# ESP32_breakout_v1.net
KiCad netlist of a schematic drawn in EAGLE
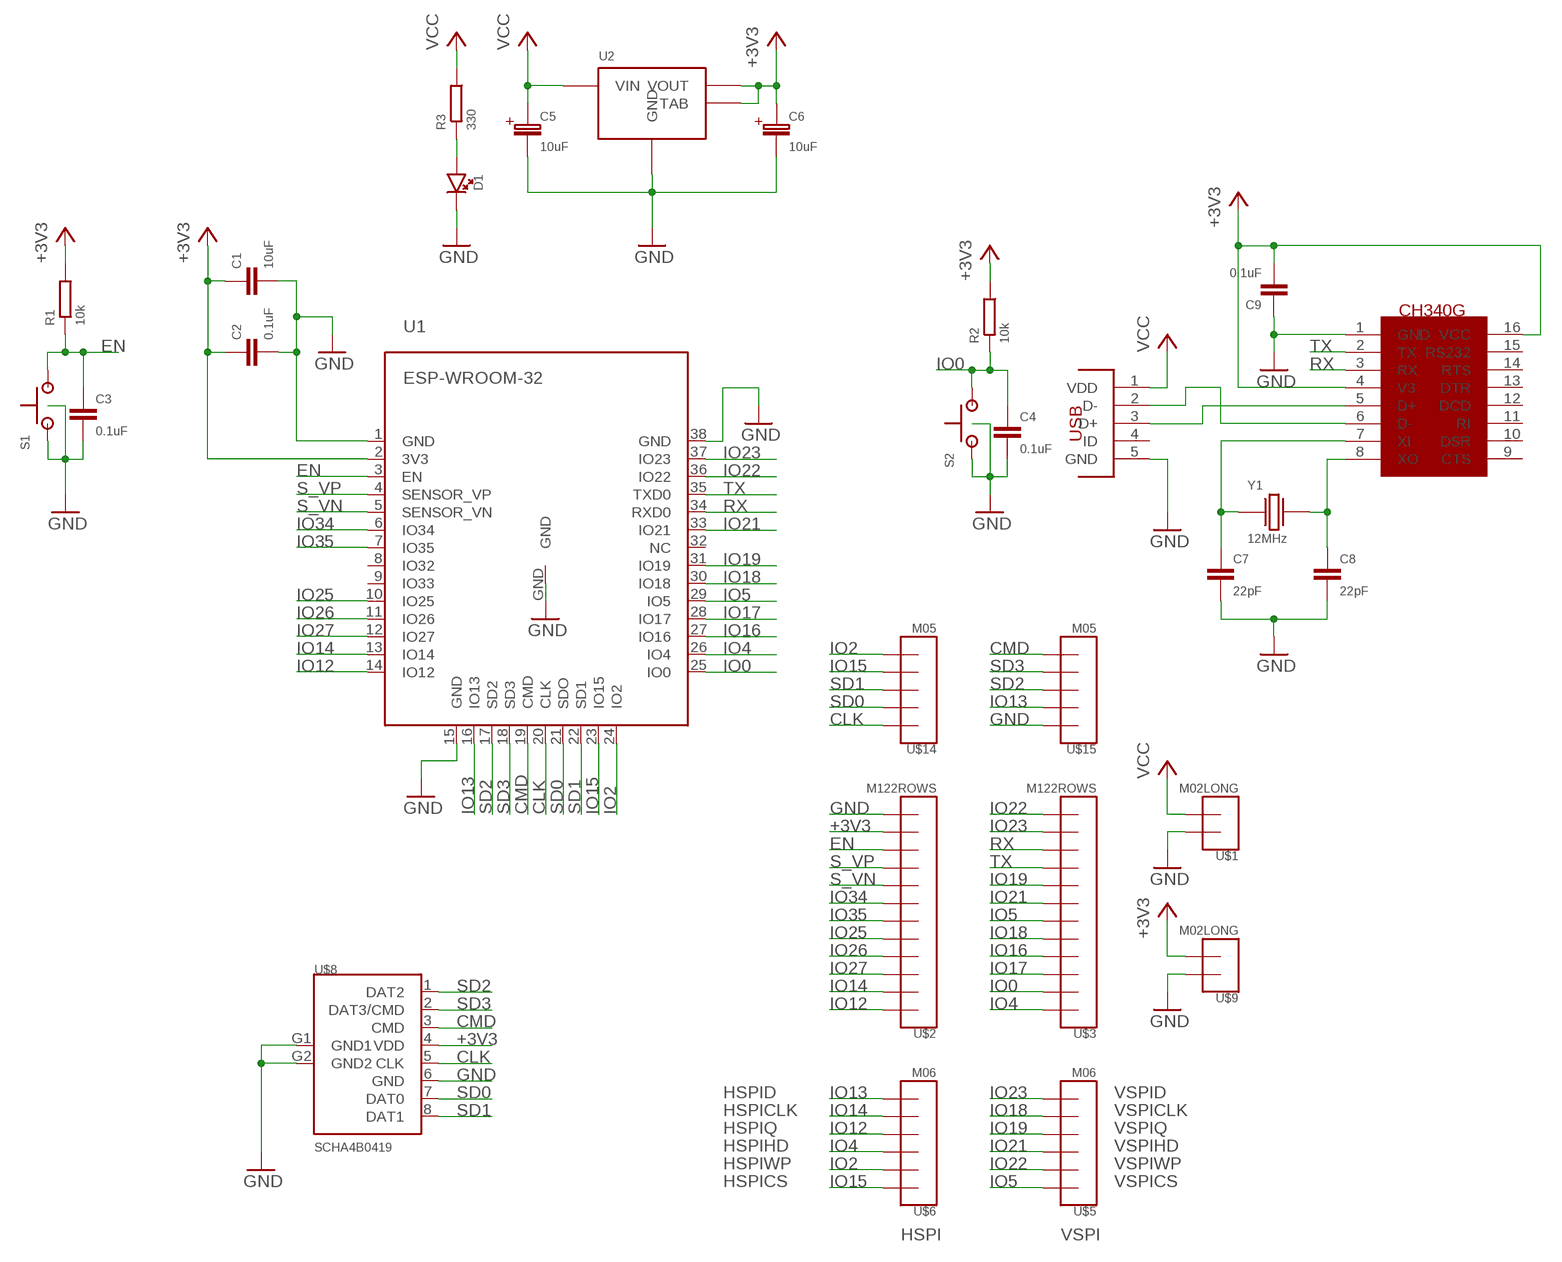
[diagram p0: schematic, sheet 1]

(export (version "E")
  (design (tool "Eeschema 10.0.6"))
  (components
    (comp (ref "C1")
      (value "10uF")
      (footprint "eagle-import:CAP-0603")
      (libsource (lib "eagle-import") (part "CAP0603"))
    )
    (comp (ref "C2")
      (value "0.1uF")
      (footprint "eagle-import:CAP-0603")
      (libsource (lib "eagle-import") (part "CAP0603"))
    )
    (comp (ref "C3")
      (value "0.1uF")
      (footprint "eagle-import:CAP-0603")
      (libsource (lib "eagle-import") (part "CAP0603"))
    )
    (comp (ref "C4")
      (value "0.1uF")
      (footprint "eagle-import:CAP-0603")
      (libsource (lib "eagle-import") (part "CAP0603"))
    )
    (comp (ref "C5")
      (value "10uF")
      (footprint "eagle-import:B-3528")
      (libsource (lib "eagle-import") (part "CAP-POLARCASEB-3528"))
    )
    (comp (ref "C6")
      (value "10uF")
      (footprint "eagle-import:B-3528")
      (libsource (lib "eagle-import") (part "CAP-POLARCASEB-3528"))
    )
    (comp (ref "C7")
      (value "22pF")
      (footprint "eagle-import:CAP-0603")
      (libsource (lib "eagle-import") (part "CAP0603"))
    )
    (comp (ref "C8")
      (value "22pF")
      (footprint "eagle-import:CAP-0603")
      (libsource (lib "eagle-import") (part "CAP0603"))
    )
    (comp (ref "C9")
      (value "0.1uF")
      (footprint "eagle-import:CAP-0603")
      (libsource (lib "eagle-import") (part "CAP0603"))
    )
    (comp (ref "D1")
      (value "LED1206")
      (footprint "eagle-import:LED-1206")
      (libsource (lib "eagle-import") (part "LED1206"))
    )
    (comp (ref "R1")
      (value "10k")
      (footprint "eagle-import:RES-0603")
      (libsource (lib "eagle-import") (part "RESISTOR0603"))
    )
    (comp (ref "R2")
      (value "10k")
      (footprint "eagle-import:RES-0603")
      (libsource (lib "eagle-import") (part "RESISTOR0603"))
    )
    (comp (ref "R3")
      (value "330")
      (footprint "eagle-import:RES-0603")
      (libsource (lib "eagle-import") (part "RESISTOR0603"))
    )
    (comp (ref "S1")
      (value "SKHMQME010")
      (footprint "eagle-import:SKHMQME010")
      (libsource (lib "eagle-import") (part "SKHMQME010"))
    )
    (comp (ref "S2")
      (value "SKHMQME010")
      (footprint "eagle-import:SKHMQME010")
      (libsource (lib "eagle-import") (part "SKHMQME010"))
    )
    (comp (ref "U$1")
      (value "M02LONG")
      (footprint "eagle-import:1X02-LONG")
      (libsource (lib "eagle-import") (part "M02LONG"))
    )
    (comp (ref "U$2")
      (value "M122ROWS")
      (footprint "eagle-import:2X06")
      (libsource (lib "eagle-import") (part "M122ROWS"))
    )
    (comp (ref "U$3")
      (value "M122ROWS")
      (footprint "eagle-import:2X06")
      (libsource (lib "eagle-import") (part "M122ROWS"))
    )
    (comp (ref "U$4")
      (value "MOLEX_USBMICRO")
      (footprint "eagle-import:MOLEX_47346-001")
      (libsource (lib "eagle-import") (part "MOLEX_USBMICRO"))
    )
    (comp (ref "U$5")
      (value "M06")
      (footprint "eagle-import:1X06")
      (libsource (lib "eagle-import") (part "M06"))
    )
    (comp (ref "U$6")
      (value "M06")
      (footprint "eagle-import:1X06")
      (libsource (lib "eagle-import") (part "M06"))
    )
    (comp (ref "U$7")
      (value "CH340G")
      (footprint "eagle-import:SOIC16")
      (libsource (lib "eagle-import") (part "CH340G"))
    )
    (comp (ref "U$8")
      (value "SCHA4B0419")
      (footprint "eagle-import:MICROSD_SCHA4B0419")
      (libsource (lib "eagle-import") (part "SCHA4B0419"))
    )
    (comp (ref "U$9")
      (value "M02LONG")
      (footprint "eagle-import:1X02-LONG")
      (libsource (lib "eagle-import") (part "M02LONG"))
    )
    (comp (ref "U$14")
      (value "M05")
      (footprint "eagle-import:1X05")
      (libsource (lib "eagle-import") (part "M05"))
    )
    (comp (ref "U$15")
      (value "M05")
      (footprint "eagle-import:1X05")
      (libsource (lib "eagle-import") (part "M05"))
    )
    (comp (ref "U1")
      (value "ESP-WROOM-32")
      (footprint "eagle-import:ESP-WROOM-32")
      (libsource (lib "eagle-import") (part "ESP-WROOM-32"))
    )
    (comp (ref "U2")
      (value "NCP-1117")
      (footprint "eagle-import:SOT-223-4")
      (libsource (lib "eagle-import") (part "NCP-1117"))
    )
    (comp (ref "Y1")
      (value "12MHz")
      (footprint "eagle-import:HC-49_US")
      (libsource (lib "eagle-import") (part "ABLS-12MHZ-B2-T"))
    )
  )
  (nets
    (net (code "1") (name "+3V3") (class "Default")
      (node (ref "C1") (pin "1") (pinfunction "1_1") (pintype "passive"))
      (node (ref "C2") (pin "1") (pinfunction "1_1") (pintype "passive"))
      (node (ref "C6") (pin "P") (pinfunction "P_P") (pintype "passive"))
      (node (ref "C9") (pin "2") (pinfunction "2_2") (pintype "passive"))
      (node (ref "R1") (pin "2") (pinfunction "2_2") (pintype "passive"))
      (node (ref "R2") (pin "2") (pinfunction "2_2") (pintype "passive"))
      (node (ref "U$2") (pin "11") (pinfunction "11_11") (pintype "bidirectional"))
      (node (ref "U$7") (pin "16") (pinfunction "VCC_16") (pintype "bidirectional"))
      (node (ref "U$7") (pin "4") (pinfunction "V3_4") (pintype "bidirectional"))
      (node (ref "U$8") (pin "4") (pinfunction "VDD_4") (pintype "bidirectional"))
      (node (ref "U$9") (pin "2") (pinfunction "2_2") (pintype "bidirectional"))
      (node (ref "U1") (pin "2") (pinfunction "3V3_2") (pintype "bidirectional"))
      (node (ref "U2") (pin "2") (pinfunction "VOUT_2") (pintype "power_in"))
      (node (ref "U2") (pin "PAD") (pinfunction "TAB_PAD") (pintype "power_in"))
    )
    (net (code "2") (name "/CLK") (class "Default")
      (node (ref "U$14") (pin "1") (pinfunction "1_1") (pintype "bidirectional"))
      (node (ref "U$8") (pin "5") (pinfunction "CLK_5") (pintype "bidirectional"))
      (node (ref "U1") (pin "20") (pinfunction "CLK_20") (pintype "bidirectional"))
    )
    (net (code "3") (name "/CMD") (class "Default")
      (node (ref "U$15") (pin "5") (pinfunction "5_5") (pintype "bidirectional"))
      (node (ref "U$8") (pin "3") (pinfunction "CMD_3") (pintype "bidirectional"))
      (node (ref "U1") (pin "19") (pinfunction "CMD_19") (pintype "bidirectional"))
    )
    (net (code "4") (name "/EN") (class "Default")
      (node (ref "C3") (pin "1") (pinfunction "1_1") (pintype "passive"))
      (node (ref "R1") (pin "1") (pinfunction "1_1") (pintype "passive"))
      (node (ref "S1") (pin "3") (pinfunction "2_3") (pintype "bidirectional"))
      (node (ref "U$2") (pin "10") (pinfunction "10_10") (pintype "bidirectional"))
      (node (ref "U1") (pin "3") (pinfunction "EN_3") (pintype "bidirectional"))
    )
    (net (code "5") (name "/IO0") (class "Default")
      (node (ref "C4") (pin "1") (pinfunction "1_1") (pintype "passive"))
      (node (ref "R2") (pin "1") (pinfunction "1_1") (pintype "passive"))
      (node (ref "S2") (pin "3") (pinfunction "2_3") (pintype "bidirectional"))
      (node (ref "U$3") (pin "2") (pinfunction "2_2") (pintype "bidirectional"))
      (node (ref "U1") (pin "25") (pinfunction "IO0_25") (pintype "bidirectional"))
    )
    (net (code "6") (name "/IO2") (class "Default")
      (node (ref "U$14") (pin "5") (pinfunction "5_5") (pintype "bidirectional"))
      (node (ref "U$6") (pin "2") (pinfunction "2_2") (pintype "bidirectional"))
      (node (ref "U1") (pin "24") (pinfunction "IO2_24") (pintype "bidirectional"))
    )
    (net (code "7") (name "/IO4") (class "Default")
      (node (ref "U$3") (pin "1") (pinfunction "1_1") (pintype "bidirectional"))
      (node (ref "U$6") (pin "3") (pinfunction "3_3") (pintype "bidirectional"))
      (node (ref "U1") (pin "26") (pinfunction "IO4_26") (pintype "bidirectional"))
    )
    (net (code "8") (name "/IO5") (class "Default")
      (node (ref "U$3") (pin "6") (pinfunction "6_6") (pintype "bidirectional"))
      (node (ref "U$5") (pin "1") (pinfunction "1_1") (pintype "bidirectional"))
      (node (ref "U1") (pin "29") (pinfunction "IO5_29") (pintype "bidirectional"))
    )
    (net (code "9") (name "/IO12") (class "Default")
      (node (ref "U$2") (pin "1") (pinfunction "1_1") (pintype "bidirectional"))
      (node (ref "U$6") (pin "4") (pinfunction "4_4") (pintype "bidirectional"))
      (node (ref "U1") (pin "14") (pinfunction "IO12_14") (pintype "bidirectional"))
    )
    (net (code "10") (name "/IO13") (class "Default")
      (node (ref "U$15") (pin "2") (pinfunction "2_2") (pintype "bidirectional"))
      (node (ref "U$6") (pin "6") (pinfunction "6_6") (pintype "bidirectional"))
      (node (ref "U1") (pin "16") (pinfunction "IO13_16") (pintype "bidirectional"))
    )
    (net (code "11") (name "/IO14") (class "Default")
      (node (ref "U$2") (pin "2") (pinfunction "2_2") (pintype "bidirectional"))
      (node (ref "U$6") (pin "5") (pinfunction "5_5") (pintype "bidirectional"))
      (node (ref "U1") (pin "13") (pinfunction "IO14_13") (pintype "bidirectional"))
    )
    (net (code "12") (name "/IO15") (class "Default")
      (node (ref "U$14") (pin "4") (pinfunction "4_4") (pintype "bidirectional"))
      (node (ref "U$6") (pin "1") (pinfunction "1_1") (pintype "bidirectional"))
      (node (ref "U1") (pin "23") (pinfunction "IO15_23") (pintype "bidirectional"))
    )
    (net (code "13") (name "/IO16") (class "Default")
      (node (ref "U$3") (pin "4") (pinfunction "4_4") (pintype "bidirectional"))
      (node (ref "U1") (pin "27") (pinfunction "IO16_27") (pintype "bidirectional"))
    )
    (net (code "14") (name "/IO17") (class "Default")
      (node (ref "U$3") (pin "3") (pinfunction "3_3") (pintype "bidirectional"))
      (node (ref "U1") (pin "28") (pinfunction "IO17_28") (pintype "bidirectional"))
    )
    (net (code "15") (name "/IO18") (class "Default")
      (node (ref "U$3") (pin "5") (pinfunction "5_5") (pintype "bidirectional"))
      (node (ref "U$5") (pin "5") (pinfunction "5_5") (pintype "bidirectional"))
      (node (ref "U1") (pin "30") (pinfunction "IO18_30") (pintype "bidirectional"))
    )
    (net (code "16") (name "/IO19") (class "Default")
      (node (ref "U$3") (pin "8") (pinfunction "8_8") (pintype "bidirectional"))
      (node (ref "U$5") (pin "4") (pinfunction "4_4") (pintype "bidirectional"))
      (node (ref "U1") (pin "31") (pinfunction "IO19_31") (pintype "bidirectional"))
    )
    (net (code "17") (name "/IO21") (class "Default")
      (node (ref "U$3") (pin "7") (pinfunction "7_7") (pintype "bidirectional"))
      (node (ref "U$5") (pin "3") (pinfunction "3_3") (pintype "bidirectional"))
      (node (ref "U1") (pin "33") (pinfunction "IO21_33") (pintype "bidirectional"))
    )
    (net (code "18") (name "/IO22") (class "Default")
      (node (ref "U$3") (pin "12") (pinfunction "12_12") (pintype "bidirectional"))
      (node (ref "U$5") (pin "2") (pinfunction "2_2") (pintype "bidirectional"))
      (node (ref "U1") (pin "36") (pinfunction "IO22_36") (pintype "bidirectional"))
    )
    (net (code "19") (name "/IO23") (class "Default")
      (node (ref "U$3") (pin "11") (pinfunction "11_11") (pintype "bidirectional"))
      (node (ref "U$5") (pin "6") (pinfunction "6_6") (pintype "bidirectional"))
      (node (ref "U1") (pin "37") (pinfunction "IO23_37") (pintype "bidirectional"))
    )
    (net (code "20") (name "/IO25") (class "Default")
      (node (ref "U$2") (pin "5") (pinfunction "5_5") (pintype "bidirectional"))
      (node (ref "U1") (pin "10") (pinfunction "IO25_10") (pintype "bidirectional"))
    )
    (net (code "21") (name "/IO26") (class "Default")
      (node (ref "U$2") (pin "4") (pinfunction "4_4") (pintype "bidirectional"))
      (node (ref "U1") (pin "11") (pinfunction "IO26_11") (pintype "bidirectional"))
    )
    (net (code "22") (name "/IO27") (class "Default")
      (node (ref "U$2") (pin "3") (pinfunction "3_3") (pintype "bidirectional"))
      (node (ref "U1") (pin "12") (pinfunction "IO27_12") (pintype "bidirectional"))
    )
    (net (code "23") (name "/IO34") (class "Default")
      (node (ref "U$2") (pin "7") (pinfunction "7_7") (pintype "bidirectional"))
      (node (ref "U1") (pin "6") (pinfunction "IO34_6") (pintype "bidirectional"))
    )
    (net (code "24") (name "/IO35") (class "Default")
      (node (ref "U$2") (pin "6") (pinfunction "6_6") (pintype "bidirectional"))
      (node (ref "U1") (pin "7") (pinfunction "IO35_7") (pintype "bidirectional"))
    )
    (net (code "25") (name "/RX") (class "Default")
      (node (ref "U$3") (pin "10") (pinfunction "10_10") (pintype "bidirectional"))
      (node (ref "U$7") (pin "3") (pinfunction "RX_3") (pintype "bidirectional"))
      (node (ref "U1") (pin "34") (pinfunction "RXD0_34") (pintype "bidirectional"))
    )
    (net (code "26") (name "/SD0") (class "Default")
      (node (ref "U$14") (pin "2") (pinfunction "2_2") (pintype "bidirectional"))
      (node (ref "U$8") (pin "7") (pinfunction "DAT0_7") (pintype "bidirectional"))
      (node (ref "U1") (pin "21") (pinfunction "SDO_21") (pintype "bidirectional"))
    )
    (net (code "27") (name "/SD1") (class "Default")
      (node (ref "U$14") (pin "3") (pinfunction "3_3") (pintype "bidirectional"))
      (node (ref "U$8") (pin "8") (pinfunction "DAT1_8") (pintype "bidirectional"))
      (node (ref "U1") (pin "22") (pinfunction "SD1_22") (pintype "bidirectional"))
    )
    (net (code "28") (name "/SD2") (class "Default")
      (node (ref "U$15") (pin "3") (pinfunction "3_3") (pintype "bidirectional"))
      (node (ref "U$8") (pin "1") (pinfunction "DAT2_1") (pintype "bidirectional"))
      (node (ref "U1") (pin "17") (pinfunction "SD2_17") (pintype "bidirectional"))
    )
    (net (code "29") (name "/SD3") (class "Default")
      (node (ref "U$15") (pin "4") (pinfunction "4_4") (pintype "bidirectional"))
      (node (ref "U$8") (pin "2") (pinfunction "DAT3/CMD_2") (pintype "bidirectional"))
      (node (ref "U1") (pin "18") (pinfunction "SD3_18") (pintype "bidirectional"))
    )
    (net (code "30") (name "/S_VN") (class "Default")
      (node (ref "U$2") (pin "8") (pinfunction "8_8") (pintype "bidirectional"))
      (node (ref "U1") (pin "5") (pinfunction "SENSOR_VN_5") (pintype "bidirectional"))
    )
    (net (code "31") (name "/S_VP") (class "Default")
      (node (ref "U$2") (pin "9") (pinfunction "9_9") (pintype "bidirectional"))
      (node (ref "U1") (pin "4") (pinfunction "SENSOR_VP_4") (pintype "bidirectional"))
    )
    (net (code "32") (name "/TX") (class "Default")
      (node (ref "U$3") (pin "9") (pinfunction "9_9") (pintype "bidirectional"))
      (node (ref "U$7") (pin "2") (pinfunction "TX_2") (pintype "bidirectional"))
      (node (ref "U1") (pin "35") (pinfunction "TXD0_35") (pintype "bidirectional"))
    )
    (net (code "33") (name "GND") (class "Default")
      (node (ref "C1") (pin "2") (pinfunction "2_2") (pintype "passive"))
      (node (ref "C2") (pin "2") (pinfunction "2_2") (pintype "passive"))
      (node (ref "C3") (pin "2") (pinfunction "2_2") (pintype "passive"))
      (node (ref "C4") (pin "2") (pinfunction "2_2") (pintype "passive"))
      (node (ref "C5") (pin "N") (pinfunction "N_N") (pintype "passive"))
      (node (ref "C6") (pin "N") (pinfunction "N_N") (pintype "passive"))
      (node (ref "C7") (pin "2") (pinfunction "2_2") (pintype "passive"))
      (node (ref "C8") (pin "2") (pinfunction "2_2") (pintype "passive"))
      (node (ref "C9") (pin "1") (pinfunction "1_1") (pintype "passive"))
      (node (ref "D1") (pin "C") (pinfunction "C_C") (pintype "bidirectional"))
      (node (ref "S1") (pin "1") (pinfunction "1_1") (pintype "bidirectional"))
      (node (ref "S1") (pin "5") (pinfunction "3_5") (pintype "bidirectional"))
      (node (ref "S2") (pin "1") (pinfunction "1_1") (pintype "bidirectional"))
      (node (ref "S2") (pin "5") (pinfunction "3_5") (pintype "bidirectional"))
      (node (ref "U$1") (pin "1") (pinfunction "1_1") (pintype "bidirectional"))
      (node (ref "U$15") (pin "1") (pinfunction "1_1") (pintype "bidirectional"))
      (node (ref "U$2") (pin "12") (pinfunction "12_12") (pintype "bidirectional"))
      (node (ref "U$4") (pin "5") (pinfunction "GND_5") (pintype "bidirectional"))
      (node (ref "U$7") (pin "1") (pinfunction "GND_1") (pintype "bidirectional"))
      (node (ref "U$8") (pin "6") (pinfunction "GND_6") (pintype "bidirectional"))
      (node (ref "U$8") (pin "G1") (pinfunction "GND1_G1") (pintype "bidirectional"))
      (node (ref "U$8") (pin "G2") (pinfunction "GND2_G2") (pintype "bidirectional"))
      (node (ref "U$9") (pin "1") (pinfunction "1_1") (pintype "bidirectional"))
      (node (ref "U1") (pin "1") (pinfunction "GND_1") (pintype "bidirectional"))
      (node (ref "U1") (pin "15") (pinfunction "GND_15") (pintype "bidirectional"))
      (node (ref "U1") (pin "38") (pinfunction "GND_38") (pintype "bidirectional"))
      (node (ref "U1") (pin "GND") (pinfunction "GND_GND") (pintype "bidirectional"))
      (node (ref "U2") (pin "1") (pinfunction "GND_1") (pintype "power_in"))
    )
    (net (code "34") (name "Net-(D1-PadA)") (class "Default")
      (node (ref "D1") (pin "A") (pinfunction "A_A") (pintype "bidirectional"))
      (node (ref "R3") (pin "1") (pinfunction "1_1") (pintype "passive"))
    )
    (net (code "35") (name "Net-(U$4-D+)") (class "Default")
      (node (ref "U$4") (pin "3") (pinfunction "D+_3") (pintype "bidirectional"))
      (node (ref "U$7") (pin "5") (pinfunction "D+_5") (pintype "bidirectional"))
    )
    (net (code "36") (name "Net-(U$4-D-)") (class "Default")
      (node (ref "U$4") (pin "2") (pinfunction "D-_2") (pintype "bidirectional"))
      (node (ref "U$7") (pin "6") (pinfunction "D-_6") (pintype "bidirectional"))
    )
    (net (code "37") (name "Net-(U$7-XI)") (class "Default")
      (node (ref "C7") (pin "1") (pinfunction "1_1") (pintype "passive"))
      (node (ref "U$7") (pin "7") (pinfunction "XI_7") (pintype "bidirectional"))
      (node (ref "Y1") (pin "P$1") (pinfunction "1_P$1") (pintype "bidirectional"))
    )
    (net (code "38") (name "Net-(U$7-XO)") (class "Default")
      (node (ref "C8") (pin "1") (pinfunction "1_1") (pintype "passive"))
      (node (ref "U$7") (pin "8") (pinfunction "XO_8") (pintype "bidirectional"))
      (node (ref "Y1") (pin "P$2") (pinfunction "2_P$2") (pintype "bidirectional"))
    )
    (net (code "39") (name "VCC") (class "Default")
      (node (ref "C5") (pin "P") (pinfunction "P_P") (pintype "passive"))
      (node (ref "R3") (pin "2") (pinfunction "2_2") (pintype "passive"))
      (node (ref "U$1") (pin "2") (pinfunction "2_2") (pintype "bidirectional"))
      (node (ref "U$4") (pin "1") (pinfunction "VDD_1") (pintype "bidirectional"))
      (node (ref "U2") (pin "3") (pinfunction "VIN_3") (pintype "power_in"))
    )
    (net (code "40") (name "unconnected-(U$4-ID-Pad4)") (class "Default")
      (node (ref "U$4") (pin "4") (pinfunction "ID_4") (pintype "bidirectional"))
    )
    (net (code "41") (name "unconnected-(U$7-CTS-Pad9)") (class "Default")
      (node (ref "U$7") (pin "9") (pinfunction "CTS_9") (pintype "bidirectional"))
    )
    (net (code "42") (name "unconnected-(U$7-DCD-Pad12)") (class "Default")
      (node (ref "U$7") (pin "12") (pinfunction "DCD_12") (pintype "bidirectional"))
    )
    (net (code "43") (name "unconnected-(U$7-DSR-Pad10)") (class "Default")
      (node (ref "U$7") (pin "10") (pinfunction "DSR_10") (pintype "bidirectional"))
    )
    (net (code "44") (name "unconnected-(U$7-DTR-Pad13)") (class "Default")
      (node (ref "U$7") (pin "13") (pinfunction "DTR_13") (pintype "bidirectional"))
    )
    (net (code "45") (name "unconnected-(U$7-RI-Pad11)") (class "Default")
      (node (ref "U$7") (pin "11") (pinfunction "RI_11") (pintype "bidirectional"))
    )
    (net (code "46") (name "unconnected-(U$7-RS232-Pad15)") (class "Default")
      (node (ref "U$7") (pin "15") (pinfunction "RS232_15") (pintype "bidirectional"))
    )
    (net (code "47") (name "unconnected-(U$7-RTS-Pad14)") (class "Default")
      (node (ref "U$7") (pin "14") (pinfunction "RTS_14") (pintype "bidirectional"))
    )
    (net (code "48") (name "unconnected-(U1-IO32-Pad8)") (class "Default")
      (node (ref "U1") (pin "8") (pinfunction "IO32_8") (pintype "bidirectional"))
    )
    (net (code "49") (name "unconnected-(U1-IO33-Pad9)") (class "Default")
      (node (ref "U1") (pin "9") (pinfunction "IO33_9") (pintype "bidirectional"))
    )
    (net (code "50") (name "unconnected-(U1-NC-Pad32)") (class "Default")
      (node (ref "U1") (pin "32") (pinfunction "NC_32") (pintype "bidirectional"))
    )
  )
)
